# GSG_TX.net
KiCad netlist of a schematic drawn in Altium Designer
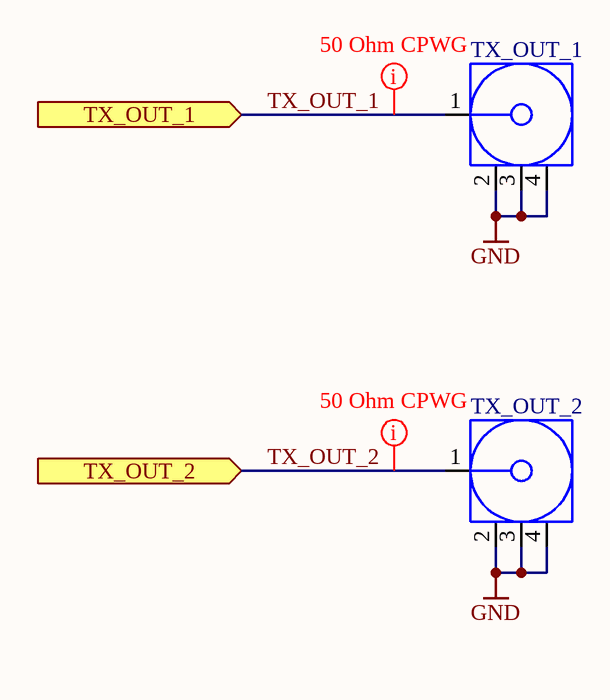
[diagram p0: GSG_TX.SchDoc]

(export (version "E")
  (design (tool "Eeschema 10.0.6"))
  (components
    (comp (ref "TX_OUT_1")
      (value "60312862112552")
      (footprint "60312862112552")
      (description "WR-SMA Connector, PCB Solderless, DC~18GHz, 50Ohm")
      (fields (field (name "MANUFACTURER") "Würth"))
      (libsource (lib "database_library") (part "60312862112552"))
    )
    (comp (ref "TX_OUT_2")
      (value "60312862112552")
      (footprint "60312862112552")
      (description "WR-SMA Connector, PCB Solderless, DC~18GHz, 50Ohm")
      (fields (field (name "MANUFACTURER") "Würth"))
      (libsource (lib "database_library") (part "60312862112552"))
    )
  )
  (nets
    (net (code "1") (name "/TX_OUT_1") (class "Default")
      (node (ref "TX_OUT_1") (pin "1") (pinfunction "Signal_1") (pintype "passive"))
    )
    (net (code "2") (name "/TX_OUT_2") (class "Default")
      (node (ref "TX_OUT_2") (pin "1") (pinfunction "Signal_1") (pintype "passive"))
    )
    (net (code "3") (name "GND") (class "Default")
      (node (ref "TX_OUT_1") (pin "2") (pinfunction "GND_2") (pintype "passive"))
      (node (ref "TX_OUT_1") (pin "3") (pinfunction "GND_3") (pintype "passive"))
      (node (ref "TX_OUT_1") (pin "4") (pinfunction "GND_4") (pintype "passive"))
      (node (ref "TX_OUT_2") (pin "2") (pinfunction "GND_2") (pintype "passive"))
      (node (ref "TX_OUT_2") (pin "3") (pinfunction "GND_3") (pintype "passive"))
      (node (ref "TX_OUT_2") (pin "4") (pinfunction "GND_4") (pintype "passive"))
    )
  )
)
